# power.net
KiCad netlist of a schematic drawn in Altium Designer
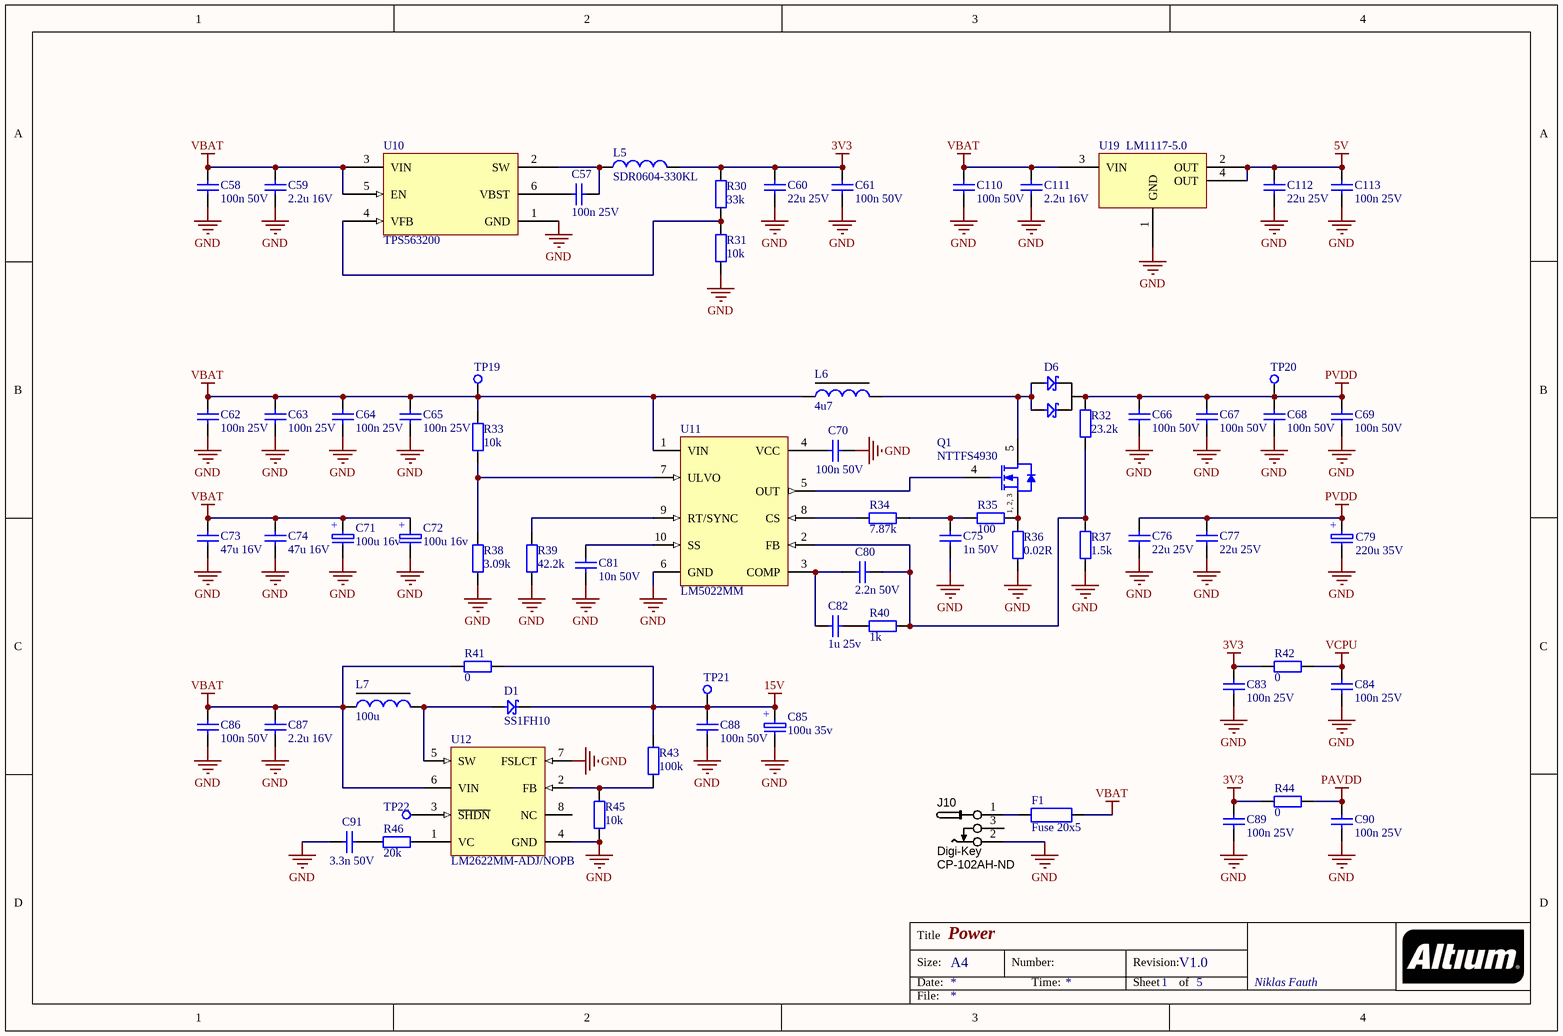
[diagram p0: power.SchDoc]

(export (version "E")
  (design (tool "Eeschema 10.0.6"))
  (components
    (comp (ref "C57")
      (value "100n 25V")
      (footprint "C-0603-H")
      (description "Capacitor 100n 25V")
      (libsource (lib "Passives") (part "C-0603-100n-25V"))
    )
    (comp (ref "C58")
      (value "100n 50V")
      (footprint "C-0603-H")
      (description "Capacitor 100n 50V")
      (libsource (lib "Passives") (part "C-0603-100n-50V"))
    )
    (comp (ref "C59")
      (value "2.2u 16V")
      (footprint "C-0603-H")
      (description "Capacitor 2.2uF 16V")
      (libsource (lib "Passives") (part "C-0603-2u2-16V"))
    )
    (comp (ref "C60")
      (value "22u 25V")
      (footprint "C-1210-M")
      (description "Capacitor 22uF 25V")
      (libsource (lib "Passives") (part "C-1210-22u-25V"))
    )
    (comp (ref "C61")
      (value "100n 50V")
      (footprint "C-0603-H")
      (description "Capacitor 100n 50V")
      (libsource (lib "Passives") (part "C-0603-100n-50V"))
    )
    (comp (ref "C62")
      (value "100n 25V")
      (footprint "C-0603-H")
      (description "Capacitor 100n 25V")
      (libsource (lib "Passives") (part "C-0603-100n-25V"))
    )
    (comp (ref "C63")
      (value "100n 25V")
      (footprint "C-0603-H")
      (description "Capacitor 100n 25V")
      (libsource (lib "Passives") (part "C-0603-100n-25V"))
    )
    (comp (ref "C64")
      (value "100n 25V")
      (footprint "C-0603-H")
      (description "Capacitor 100n 25V")
      (libsource (lib "Passives") (part "C-0603-100n-25V"))
    )
    (comp (ref "C65")
      (value "100n 25V")
      (footprint "C-0603-H")
      (description "Capacitor 100n 25V")
      (libsource (lib "Passives") (part "C-0603-100n-25V"))
    )
    (comp (ref "C66")
      (value "100n 50V")
      (footprint "C-0603-H")
      (description "Capacitor 100n 50V")
      (libsource (lib "Passives") (part "C-0603-100n-50V"))
    )
    (comp (ref "C67")
      (value "100n 50V")
      (footprint "C-0603-H")
      (description "Capacitor 100n 50V")
      (libsource (lib "Passives") (part "C-0603-100n-50V"))
    )
    (comp (ref "C68")
      (value "100n 50V")
      (footprint "C-0603-H")
      (description "Capacitor 100n 50V")
      (libsource (lib "Passives") (part "C-0603-100n-50V"))
    )
    (comp (ref "C69")
      (value "100n 50V")
      (footprint "C-0603-H")
      (description "Capacitor 100n 50V")
      (libsource (lib "Passives") (part "C-0603-100n-50V"))
    )
    (comp (ref "C70")
      (value "100n 50V")
      (footprint "C-0603-H")
      (description "Capacitor 100n 50V")
      (libsource (lib "Passives") (part "C-0603-100n-50V"))
    )
    (comp (ref "C71")
      (value "100u 16v")
      (footprint "SMD-6.3-5.4")
      (description "electrolytic capacitor 100uF 16V")
      (libsource (lib "Passives") (part "CE-SMD-100u-16V"))
    )
    (comp (ref "C72")
      (value "100u 16v")
      (footprint "SMD-6.3-5.4")
      (description "electrolytic capacitor 100uF 16V")
      (libsource (lib "Passives") (part "CE-SMD-100u-16V"))
    )
    (comp (ref "C73")
      (value "47u 16V")
      (footprint "C-1210-M")
      (description "Capacitor 47uF 16V")
      (libsource (lib "Passives") (part "C-1210-47u-16V"))
    )
    (comp (ref "C74")
      (value "47u 16V")
      (footprint "C-1210-M")
      (description "Capacitor 47uF 16V")
      (libsource (lib "Passives") (part "C-1210-47u-16V"))
    )
    (comp (ref "C75")
      (value "1n 50V")
      (footprint "C-0603-H")
      (description "Capacitor 1nF 50V")
      (libsource (lib "Passives") (part "C-0603-1n-50V"))
    )
    (comp (ref "C76")
      (value "22u 25V")
      (footprint "C-1210-M")
      (description "Capacitor 22uF 25V")
      (libsource (lib "Passives") (part "C-1210-22u-25V"))
    )
    (comp (ref "C77")
      (value "22u 25V")
      (footprint "C-1210-M")
      (description "Capacitor 22uF 25V")
      (libsource (lib "Passives") (part "C-1210-22u-25V"))
    )
    (comp (ref "C79")
      (value "220u 35V")
      (footprint "SMD-10x10")
      (description "electrolytic capacitor 220u 35V")
      (libsource (lib "Passives") (part "CE-SMD-220u-35V"))
    )
    (comp (ref "C80")
      (value "2.2n 50V")
      (footprint "C-0603-H")
      (description "Capacitor 2.2n 50V")
      (libsource (lib "Passives") (part "C-0603-2n2-50V"))
    )
    (comp (ref "C81")
      (value "10n 50V")
      (footprint "C-0603-H")
      (description "Capacitor 10nF 50V")
      (libsource (lib "Passives") (part "C-0603-10n-50V"))
    )
    (comp (ref "C82")
      (value "1u 25v")
      (footprint "C-0603-H")
      (description "Capacitor 1uF 25V")
      (libsource (lib "Passives") (part "C-0603-1u-25V"))
    )
    (comp (ref "C83")
      (value "100n 25V")
      (footprint "C-0603-H")
      (description "Capacitor 100n 25V")
      (libsource (lib "Passives") (part "C-0603-100n-25V"))
    )
    (comp (ref "C84")
      (value "100n 25V")
      (footprint "C-0603-H")
      (description "Capacitor 100n 25V")
      (libsource (lib "Passives") (part "C-0603-100n-25V"))
    )
    (comp (ref "C85")
      (value "100u 35v")
      (footprint "SMD-6.3-7.7")
      (description "electrolytic capacitor 100uF 35V")
      (libsource (lib "Passives") (part "CE-SMD-100u-35V"))
    )
    (comp (ref "C86")
      (value "100n 50V")
      (footprint "C-0603-H")
      (description "Capacitor 100n 50V")
      (libsource (lib "Passives") (part "C-0603-100n-50V"))
    )
    (comp (ref "C87")
      (value "2.2u 16V")
      (footprint "C-0603-H")
      (description "Capacitor 2.2uF 16V")
      (libsource (lib "Passives") (part "C-0603-2u2-16V"))
    )
    (comp (ref "C88")
      (value "100n 50V")
      (footprint "C-0603-H")
      (description "Capacitor 100n 50V")
      (libsource (lib "Passives") (part "C-0603-100n-50V"))
    )
    (comp (ref "C89")
      (value "100n 25V")
      (footprint "C-0603-H")
      (description "Capacitor 100n 25V")
      (libsource (lib "Passives") (part "C-0603-100n-25V"))
    )
    (comp (ref "C90")
      (value "100n 25V")
      (footprint "C-0603-H")
      (description "Capacitor 100n 25V")
      (libsource (lib "Passives") (part "C-0603-100n-25V"))
    )
    (comp (ref "C91")
      (value "3.3n 50V")
      (footprint "C-0603-H")
      (description "Capacitor 3.3n 50V")
      (libsource (lib "Passives") (part "C-0603-3n3-50V"))
    )
    (comp (ref "C110")
      (value "100n 50V")
      (footprint "C-0603-H")
      (description "Capacitor 100n 50V")
      (libsource (lib "Passives") (part "C-0603-100n-50V"))
    )
    (comp (ref "C111")
      (value "2.2u 16V")
      (footprint "C-0603-H")
      (description "Capacitor 2.2uF 16V")
      (libsource (lib "Passives") (part "C-0603-2u2-16V"))
    )
    (comp (ref "C112")
      (value "22u 25V")
      (footprint "C-1210-M")
      (description "Capacitor 22uF 25V")
      (libsource (lib "Passives") (part "C-1210-22u-25V"))
    )
    (comp (ref "C113")
      (value "100n 25V")
      (footprint "C-0603-H")
      (description "Capacitor 100n 25V")
      (libsource (lib "Passives") (part "C-0603-100n-25V"))
    )
    (comp (ref "D1")
      (value "SS1FH10")
      (footprint "DO-219AB (SMF)")
      (libsource (lib "advanced") (part "D-SS1FH10"))
    )
    (comp (ref "D6")
      (value "6CWQ06FN")
      (footprint "TO-277A")
      (description "SS10PH10")
      (libsource (lib "advanced") (part "D-SS10PH10"))
    )
    (comp (ref "F1")
      (value "Fuse 20x5")
      (footprint "FUSE-22.5")
      (libsource (lib "advanced") (part "FUSE-20x5"))
    )
    (comp (ref "J10")
      (value "CONN_PWR_JACK_2.1x5.5mm")
      (footprint "CONN_PWR_JACK_2.1x5.5mm")
      (description "Power Connector, THT, 2.1mm ID, 5.5mm OD")
      (fields (field (name "SUPPLIER 1") "Digi-Key") (field (name "SUPPLIER PART NUMBER 1") "CP-102AH-ND"))
      (libsource (lib "PBL - Connectors") (part "CONN_PWR_JACK_2.1x5.5mm"))
    )
    (comp (ref "L5")
      (value "SDR0604-330KL")
      (footprint "SDR0604")
      (libsource (lib "Passives") (part "L-SDR0604-330KL"))
    )
    (comp (ref "L6")
      (value "4u7")
      (footprint "SRP1250")
      (description "SRP1250-472")
      (libsource (lib "Passives") (part "L-4u7-SRP1250"))
    )
    (comp (ref "L7")
      (value "100u")
      (footprint "SRN6028")
      (description "SRN6028-101M")
      (libsource (lib "Passives") (part "L-100u-SRN6028"))
    )
    (comp (ref "Q1")
      (value "NTTFS4930")
      (footprint "ONSC-WDFN-8-511AB_V")
      (description "Power MOSFET, 30 V, 23 A, Single N-Channel, 8-Pin WDFN, Pb-Free, Tape and Reel")
      (fields (field (name "PARTNUMBER") "NTTFS4930NTAG") (field (name "MANUFACTURER") "On Semiconductor"))
      (libsource (lib "Altium Content Vault") (part "CMP-1058-01046-1"))
    )
    (comp (ref "R30")
      (value "33k")
      (footprint "R-0603-H")
      (description "Resistor 33k")
      (libsource (lib "Passives") (part "R-0603-33k"))
    )
    (comp (ref "R31")
      (value "10k")
      (footprint "R-0603-H")
      (description "Resistor 10k")
      (libsource (lib "") (part "R-0603-10k_1"))
    )
    (comp (ref "R32")
      (value "23.2k")
      (footprint "R-0603-M")
      (description "Resistor 23k3")
      (libsource (lib "Passives") (part "R-0603-23k3"))
    )
    (comp (ref "R33")
      (value "10k")
      (footprint "R-0603-H")
      (description "Resistor 10k")
      (libsource (lib "") (part "R-0603-10k_1"))
    )
    (comp (ref "R34")
      (value "7.87k")
      (footprint "R-0603-M")
      (description "Resistor 7.87k")
      (libsource (lib "Passives") (part "R-0603-7k87"))
    )
    (comp (ref "R35")
      (value "100")
      (footprint "R-0603-M")
      (description "Resistor 100")
      (libsource (lib "Passives") (part "R-0603-100"))
    )
    (comp (ref "R36")
      (value "0.02R")
      (footprint "R-1206-M")
      (description "Resistor 0.02")
      (libsource (lib "Passives") (part "R-1206-0R02"))
    )
    (comp (ref "R37")
      (value "1.5k")
      (footprint "R-0603-M")
      (description "Resistor 1.5k")
      (libsource (lib "Passives") (part "R-0603-1k5"))
    )
    (comp (ref "R38")
      (value "3.09k")
      (footprint "R-0603-M")
      (description "Resistor 3.09k")
      (libsource (lib "Passives") (part "R-0603-3k09"))
    )
    (comp (ref "R39")
      (value "42.2k")
      (footprint "R-0603-M")
      (description "Resistor 42.2k")
      (libsource (lib "Passives") (part "R-0603-42k2"))
    )
    (comp (ref "R40")
      (value "1k")
      (footprint "R-0603-M")
      (description "Resistor 1k")
      (libsource (lib "Passives") (part "R-0603-1k"))
    )
    (comp (ref "R41")
      (value "0")
      (footprint "R-0603-M")
      (description "Resistor 0")
      (libsource (lib "Passives") (part "R-0603-0"))
    )
    (comp (ref "R42")
      (value "0")
      (footprint "R-0603-M")
      (description "Resistor 0")
      (libsource (lib "Passives") (part "R-0603-0"))
    )
    (comp (ref "R43")
      (value "100k")
      (footprint "R-0603-M")
      (description "Resistor 100k")
      (libsource (lib "Passives") (part "R-0603-100k"))
    )
    (comp (ref "R44")
      (value "0")
      (footprint "R-0603-M")
      (description "Resistor 0")
      (libsource (lib "Passives") (part "R-0603-0"))
    )
    (comp (ref "R45")
      (value "10k")
      (footprint "R-0603-H")
      (description "Resistor 10k")
      (libsource (lib "Passives") (part "R-0603-10k"))
    )
    (comp (ref "R46")
      (value "20k")
      (footprint "R-0603-M")
      (description "Resistor 20k")
      (libsource (lib "Passives") (part "R-0603-20k"))
    )
    (comp (ref "TP19") (value "TP-SMD") (footprint "TP") (libsource (lib "advanced") (part "TP-SMD")))
    (comp (ref "TP20") (value "TP-SMD") (footprint "TP") (libsource (lib "advanced") (part "TP-SMD")))
    (comp (ref "TP21") (value "TP-SMD") (footprint "TP") (libsource (lib "advanced") (part "TP-SMD")))
    (comp (ref "TP22") (value "TP-SMD") (footprint "TP") (libsource (lib "advanced") (part "TP-SMD")))
    (comp (ref "U10")
      (value "TPS563200")
      (footprint "SOT23-6")
      (description "4.5-V To 17-V Input, 3-A Synchronous Step-Down Voltage Regulator")
      (libsource (lib "advanced") (part "TPS563200"))
    )
    (comp (ref "U11")
      (value "LM5022MM")
      (footprint "DGS0010A_M")
      (description "60V Low Side Controller for Boost and SEPIC, 10-pin MSOP")
      (fields (field (name "MANUFACTURER") "Texas Instruments"))
      (libsource (lib "Altium Content Vault") (part "PM-CNTL-LM5020-10"))
    )
    (comp (ref "U12")
      (value "LM2622MM-ADJ/NOPB")
      (footprint "DGK0008A_L")
      (description "600kHz/1.3MHz Step-up PWM DC/DC Converter, 8-pin MSOP, Pb-Free")
      (fields (field (name "MANUFACTURER") "Texas Instruments"))
      (libsource (lib "Altium Content Vault") (part "PM-CNTL-LM2622MM-8"))
    )
    (comp (ref "U19")
      (value "LM1117-5.0")
      (footprint "SOT-223")
      (description "5V voltage regulator")
      (libsource (lib "advanced") (part "LM1117-5.0"))
    )
  )
  (nets
    (net (code "1") (name "3V3") (class "Default")
      (node (ref "C60") (pin "2") (pinfunction "2_2") (pintype "passive"))
      (node (ref "C61") (pin "2") (pinfunction "2_2") (pintype "passive"))
      (node (ref "C83") (pin "2") (pinfunction "2_2") (pintype "passive"))
      (node (ref "C89") (pin "2") (pinfunction "2_2") (pintype "passive"))
      (node (ref "L5") (pin "2") (pinfunction "2_2") (pintype "passive"))
      (node (ref "R30") (pin "2") (pinfunction "2_2") (pintype "passive"))
      (node (ref "R42") (pin "1") (pinfunction "1_1") (pintype "passive"))
      (node (ref "R44") (pin "1") (pinfunction "1_1") (pintype "passive"))
    )
    (net (code "2") (name "5V") (class "Default")
      (node (ref "C112") (pin "2") (pinfunction "2_2") (pintype "passive"))
      (node (ref "C113") (pin "2") (pinfunction "2_2") (pintype "passive"))
      (node (ref "U19") (pin "2") (pinfunction "OUT_2") (pintype "passive"))
      (node (ref "U19") (pin "4") (pinfunction "OUT_4") (pintype "passive"))
    )
    (net (code "3") (name "15V") (class "Default")
      (node (ref "C85") (pin "2") (pinfunction "2_2") (pintype "passive"))
      (node (ref "C88") (pin "1") (pinfunction "1_1") (pintype "passive"))
      (node (ref "D1") (pin "2") (pinfunction "kt_2") (pintype "passive"))
      (node (ref "R41") (pin "2") (pinfunction "2_2") (pintype "passive"))
      (node (ref "R43") (pin "2") (pinfunction "2_2") (pintype "passive"))
      (node (ref "TP21") (pin "1") (pintype "passive"))
    )
    (net (code "4") (name "GND") (class "Default")
      (node (ref "C110") (pin "1") (pinfunction "1_1") (pintype "passive"))
      (node (ref "C111") (pin "1") (pinfunction "1_1") (pintype "passive"))
      (node (ref "C112") (pin "1") (pinfunction "1_1") (pintype "passive"))
      (node (ref "C113") (pin "1") (pinfunction "1_1") (pintype "passive"))
      (node (ref "C58") (pin "1") (pinfunction "1_1") (pintype "passive"))
      (node (ref "C59") (pin "1") (pinfunction "1_1") (pintype "passive"))
      (node (ref "C60") (pin "1") (pinfunction "1_1") (pintype "passive"))
      (node (ref "C61") (pin "1") (pinfunction "1_1") (pintype "passive"))
      (node (ref "C62") (pin "1") (pinfunction "1_1") (pintype "passive"))
      (node (ref "C63") (pin "1") (pinfunction "1_1") (pintype "passive"))
      (node (ref "C64") (pin "1") (pinfunction "1_1") (pintype "passive"))
      (node (ref "C65") (pin "1") (pinfunction "1_1") (pintype "passive"))
      (node (ref "C66") (pin "1") (pinfunction "1_1") (pintype "passive"))
      (node (ref "C67") (pin "1") (pinfunction "1_1") (pintype "passive"))
      (node (ref "C68") (pin "1") (pinfunction "1_1") (pintype "passive"))
      (node (ref "C69") (pin "1") (pinfunction "1_1") (pintype "passive"))
      (node (ref "C70") (pin "2") (pinfunction "2_2") (pintype "passive"))
      (node (ref "C71") (pin "1") (pinfunction "1_1") (pintype "passive"))
      (node (ref "C72") (pin "1") (pinfunction "1_1") (pintype "passive"))
      (node (ref "C73") (pin "1") (pinfunction "1_1") (pintype "passive"))
      (node (ref "C74") (pin "1") (pinfunction "1_1") (pintype "passive"))
      (node (ref "C75") (pin "1") (pinfunction "1_1") (pintype "passive"))
      (node (ref "C76") (pin "1") (pinfunction "1_1") (pintype "passive"))
      (node (ref "C77") (pin "1") (pinfunction "1_1") (pintype "passive"))
      (node (ref "C79") (pin "1") (pinfunction "1_1") (pintype "passive"))
      (node (ref "C81") (pin "1") (pinfunction "1_1") (pintype "passive"))
      (node (ref "C83") (pin "1") (pinfunction "1_1") (pintype "passive"))
      (node (ref "C84") (pin "1") (pinfunction "1_1") (pintype "passive"))
      (node (ref "C85") (pin "1") (pinfunction "1_1") (pintype "passive"))
      (node (ref "C86") (pin "1") (pinfunction "1_1") (pintype "passive"))
      (node (ref "C87") (pin "1") (pinfunction "1_1") (pintype "passive"))
      (node (ref "C88") (pin "2") (pinfunction "2_2") (pintype "passive"))
      (node (ref "C89") (pin "1") (pinfunction "1_1") (pintype "passive"))
      (node (ref "C90") (pin "1") (pinfunction "1_1") (pintype "passive"))
      (node (ref "C91") (pin "1") (pinfunction "1_1") (pintype "passive"))
      (node (ref "J10") (pin "2") (pinfunction "2_2") (pintype "passive"))
      (node (ref "R31") (pin "1") (pinfunction "1_1") (pintype "passive"))
      (node (ref "R36") (pin "1") (pinfunction "1_1") (pintype "passive"))
      (node (ref "R37") (pin "1") (pinfunction "1_1") (pintype "passive"))
      (node (ref "R38") (pin "1") (pinfunction "1_1") (pintype "passive"))
      (node (ref "R39") (pin "1") (pinfunction "1_1") (pintype "passive"))
      (node (ref "R45") (pin "2") (pinfunction "2_2") (pintype "passive"))
      (node (ref "U10") (pin "1") (pinfunction "GND_1") (pintype "passive"))
      (node (ref "U11") (pin "6") (pinfunction "GND_6") (pintype "power_in"))
      (node (ref "U12") (pin "4") (pinfunction "GND_4") (pintype "power_in"))
      (node (ref "U12") (pin "7") (pinfunction "FSLCT_7") (pintype "input"))
      (node (ref "U19") (pin "1") (pinfunction "GND_1") (pintype "passive"))
    )
    (net (code "5") (name "Net-(C75-Pad2)") (class "Default")
      (node (ref "C75") (pin "2") (pinfunction "2_2") (pintype "passive"))
      (node (ref "R34") (pin "2") (pinfunction "2_2") (pintype "passive"))
      (node (ref "R35") (pin "1") (pinfunction "1_1") (pintype "passive"))
    )
    (net (code "6") (name "Net-(C82-Pad1)") (class "Default")
      (node (ref "C82") (pin "1") (pinfunction "1_1") (pintype "passive"))
      (node (ref "R40") (pin "2") (pinfunction "2_2") (pintype "passive"))
    )
    (net (code "7") (name "Net-(C91-Pad2)") (class "Default")
      (node (ref "C91") (pin "2") (pinfunction "2_2") (pintype "passive"))
      (node (ref "R46") (pin "1") (pinfunction "1_1") (pintype "passive"))
    )
    (net (code "8") (name "Net-(D1-an)") (class "Default")
      (node (ref "D1") (pin "1") (pinfunction "an_1") (pintype "passive"))
      (node (ref "L7") (pin "2") (pinfunction "2_2") (pintype "passive"))
      (node (ref "U12") (pin "5") (pinfunction "SW_5") (pintype "input"))
    )
    (net (code "9") (name "Net-(D6-an1)") (class "Default")
      (node (ref "D6") (pin "1") (pinfunction "an1_1") (pintype "passive"))
      (node (ref "D6") (pin "3") (pinfunction "an2_3") (pintype "passive"))
      (node (ref "L6") (pin "2") (pinfunction "2_2") (pintype "passive"))
      (node (ref "Q1") (pin "5") (pinfunction "D_5") (pintype "passive"))
    )
    (net (code "10") (name "Net-(F1-V+-Pad1)") (class "Default")
      (node (ref "F1") (pin "1") (pinfunction "V+_1") (pintype "passive"))
      (node (ref "J10") (pin "1") (pinfunction "1_1") (pintype "passive"))
    )
    (net (code "11") (name "Net-(Q1-G)") (class "Default")
      (node (ref "Q1") (pin "4") (pinfunction "G_4") (pintype "passive"))
      (node (ref "U11") (pin "5") (pinfunction "OUT_5") (pintype "output"))
    )
    (net (code "12") (name "Net-(Q1-S-Pad1)") (class "Default")
      (node (ref "Q1") (pin "1") (pinfunction "S_1") (pintype "passive"))
      (node (ref "Q1") (pin "2") (pinfunction "S_2") (pintype "passive"))
      (node (ref "Q1") (pin "3") (pinfunction "S_3") (pintype "passive"))
      (node (ref "R35") (pin "2") (pinfunction "2_2") (pintype "passive"))
      (node (ref "R36") (pin "2") (pinfunction "2_2") (pintype "passive"))
    )
    (net (code "13") (name "Net-(U10-SW)") (class "Default")
      (node (ref "C57") (pin "1") (pinfunction "1_1") (pintype "passive"))
      (node (ref "L5") (pin "1") (pinfunction "1_1") (pintype "passive"))
      (node (ref "U10") (pin "2") (pinfunction "SW_2") (pintype "passive"))
    )
    (net (code "14") (name "Net-(U10-VBST)") (class "Default")
      (node (ref "C57") (pin "2") (pinfunction "2_2") (pintype "passive"))
      (node (ref "U10") (pin "6") (pinfunction "VBST_6") (pintype "passive"))
    )
    (net (code "15") (name "Net-(U10-VFB)") (class "Default")
      (node (ref "R30") (pin "1") (pinfunction "1_1") (pintype "passive"))
      (node (ref "R31") (pin "2") (pinfunction "2_2") (pintype "passive"))
      (node (ref "U10") (pin "4") (pinfunction "VFB_4") (pintype "input"))
    )
    (net (code "16") (name "Net-(U11-COMP)") (class "Default")
      (node (ref "C80") (pin "2") (pinfunction "2_2") (pintype "passive"))
      (node (ref "C82") (pin "2") (pinfunction "2_2") (pintype "passive"))
      (node (ref "U11") (pin "3") (pinfunction "COMP_3") (pintype "passive"))
    )
    (net (code "17") (name "Net-(U11-CS)") (class "Default")
      (node (ref "R34") (pin "1") (pinfunction "1_1") (pintype "passive"))
      (node (ref "U11") (pin "8") (pinfunction "CS_8") (pintype "input"))
    )
    (net (code "18") (name "Net-(U11-FB)") (class "Default")
      (node (ref "C80") (pin "1") (pinfunction "1_1") (pintype "passive"))
      (node (ref "R32") (pin "1") (pinfunction "1_1") (pintype "passive"))
      (node (ref "R37") (pin "2") (pinfunction "2_2") (pintype "passive"))
      (node (ref "R40") (pin "1") (pinfunction "1_1") (pintype "passive"))
      (node (ref "U11") (pin "2") (pinfunction "FB_2") (pintype "input"))
    )
    (net (code "19") (name "Net-(U11-RT{slash}SYNC)") (class "Default")
      (node (ref "R39") (pin "2") (pinfunction "2_2") (pintype "passive"))
      (node (ref "U11") (pin "9") (pinfunction "RT/SYNC_9") (pintype "input"))
    )
    (net (code "20") (name "Net-(U11-SS)") (class "Default")
      (node (ref "C81") (pin "2") (pinfunction "2_2") (pintype "passive"))
      (node (ref "U11") (pin "10") (pinfunction "SS_10") (pintype "input"))
    )
    (net (code "21") (name "Net-(U11-ULVO)") (class "Default")
      (node (ref "R33") (pin "1") (pinfunction "1_1") (pintype "passive"))
      (node (ref "R38") (pin "2") (pinfunction "2_2") (pintype "passive"))
      (node (ref "U11") (pin "7") (pinfunction "ULVO_7") (pintype "input"))
    )
    (net (code "22") (name "Net-(U11-VCC)") (class "Default")
      (node (ref "C70") (pin "1") (pinfunction "1_1") (pintype "passive"))
      (node (ref "U11") (pin "4") (pinfunction "VCC_4") (pintype "power_in"))
    )
    (net (code "23") (name "Net-(U12-FB)") (class "Default")
      (node (ref "R43") (pin "1") (pinfunction "1_1") (pintype "passive"))
      (node (ref "R45") (pin "1") (pinfunction "1_1") (pintype "passive"))
      (node (ref "U12") (pin "2") (pinfunction "FB_2") (pintype "input"))
    )
    (net (code "24") (name "Net-(U12-VC)") (class "Default")
      (node (ref "R46") (pin "2") (pinfunction "2_2") (pintype "passive"))
      (node (ref "U12") (pin "1") (pinfunction "VC_1") (pintype "power_in"))
    )
    (net (code "25") (name "Net-(U12-~{SHDN})") (class "Default")
      (node (ref "TP22") (pin "1") (pintype "passive"))
      (node (ref "U12") (pin "3") (pinfunction "~{SHDN}_3") (pintype "input"))
    )
    (net (code "26") (name "PAVDD") (class "Default")
      (node (ref "C90") (pin "2") (pinfunction "2_2") (pintype "passive"))
      (node (ref "R44") (pin "2") (pinfunction "2_2") (pintype "passive"))
    )
    (net (code "27") (name "PVDD") (class "Default")
      (node (ref "C66") (pin "2") (pinfunction "2_2") (pintype "passive"))
      (node (ref "C67") (pin "2") (pinfunction "2_2") (pintype "passive"))
      (node (ref "C68") (pin "2") (pinfunction "2_2") (pintype "passive"))
      (node (ref "C69") (pin "2") (pinfunction "2_2") (pintype "passive"))
      (node (ref "C76") (pin "2") (pinfunction "2_2") (pintype "passive"))
      (node (ref "C77") (pin "2") (pinfunction "2_2") (pintype "passive"))
      (node (ref "C79") (pin "2") (pinfunction "2_2") (pintype "passive"))
      (node (ref "D6") (pin "2") (pinfunction "Ka_2") (pintype "passive"))
      (node (ref "R32") (pin "2") (pinfunction "2_2") (pintype "passive"))
      (node (ref "TP20") (pin "1") (pintype "passive"))
    )
    (net (code "28") (name "VBAT") (class "Default")
      (node (ref "C110") (pin "2") (pinfunction "2_2") (pintype "passive"))
      (node (ref "C111") (pin "2") (pinfunction "2_2") (pintype "passive"))
      (node (ref "C58") (pin "2") (pinfunction "2_2") (pintype "passive"))
      (node (ref "C59") (pin "2") (pinfunction "2_2") (pintype "passive"))
      (node (ref "C62") (pin "2") (pinfunction "2_2") (pintype "passive"))
      (node (ref "C63") (pin "2") (pinfunction "2_2") (pintype "passive"))
      (node (ref "C64") (pin "2") (pinfunction "2_2") (pintype "passive"))
      (node (ref "C65") (pin "2") (pinfunction "2_2") (pintype "passive"))
      (node (ref "C71") (pin "2") (pinfunction "2_2") (pintype "passive"))
      (node (ref "C72") (pin "2") (pinfunction "2_2") (pintype "passive"))
      (node (ref "C73") (pin "2") (pinfunction "2_2") (pintype "passive"))
      (node (ref "C74") (pin "2") (pinfunction "2_2") (pintype "passive"))
      (node (ref "C86") (pin "2") (pinfunction "2_2") (pintype "passive"))
      (node (ref "C87") (pin "2") (pinfunction "2_2") (pintype "passive"))
      (node (ref "F1") (pin "2") (pinfunction "V+_2") (pintype "passive"))
      (node (ref "L6") (pin "1") (pinfunction "1_1") (pintype "passive"))
      (node (ref "L7") (pin "1") (pinfunction "1_1") (pintype "passive"))
      (node (ref "R33") (pin "2") (pinfunction "2_2") (pintype "passive"))
      (node (ref "R41") (pin "1") (pinfunction "1_1") (pintype "passive"))
      (node (ref "TP19") (pin "1") (pintype "passive"))
      (node (ref "U10") (pin "3") (pinfunction "VIN_3") (pintype "passive"))
      (node (ref "U10") (pin "5") (pinfunction "EN_5") (pintype "input"))
      (node (ref "U11") (pin "1") (pinfunction "VIN_1") (pintype "power_in"))
      (node (ref "U12") (pin "6") (pinfunction "VIN_6") (pintype "power_in"))
      (node (ref "U19") (pin "3") (pinfunction "VIN_3") (pintype "passive"))
    )
    (net (code "29") (name "VCPU") (class "Default")
      (node (ref "C84") (pin "2") (pinfunction "2_2") (pintype "passive"))
      (node (ref "R42") (pin "2") (pinfunction "2_2") (pintype "passive"))
    )
    (net (code "30") (name "unconnected-(J10-Pad3)") (class "Default")
      (node (ref "J10") (pin "3") (pinfunction "3_3") (pintype "passive"))
    )
    (net (code "31") (name "unconnected-(U12-NC-Pad8)") (class "Default")
      (node (ref "U12") (pin "8") (pinfunction "NC_8") (pintype "passive"))
    )
  )
)
